# 1_BLE.net
KiCad netlist of a schematic drawn in Altium Designer
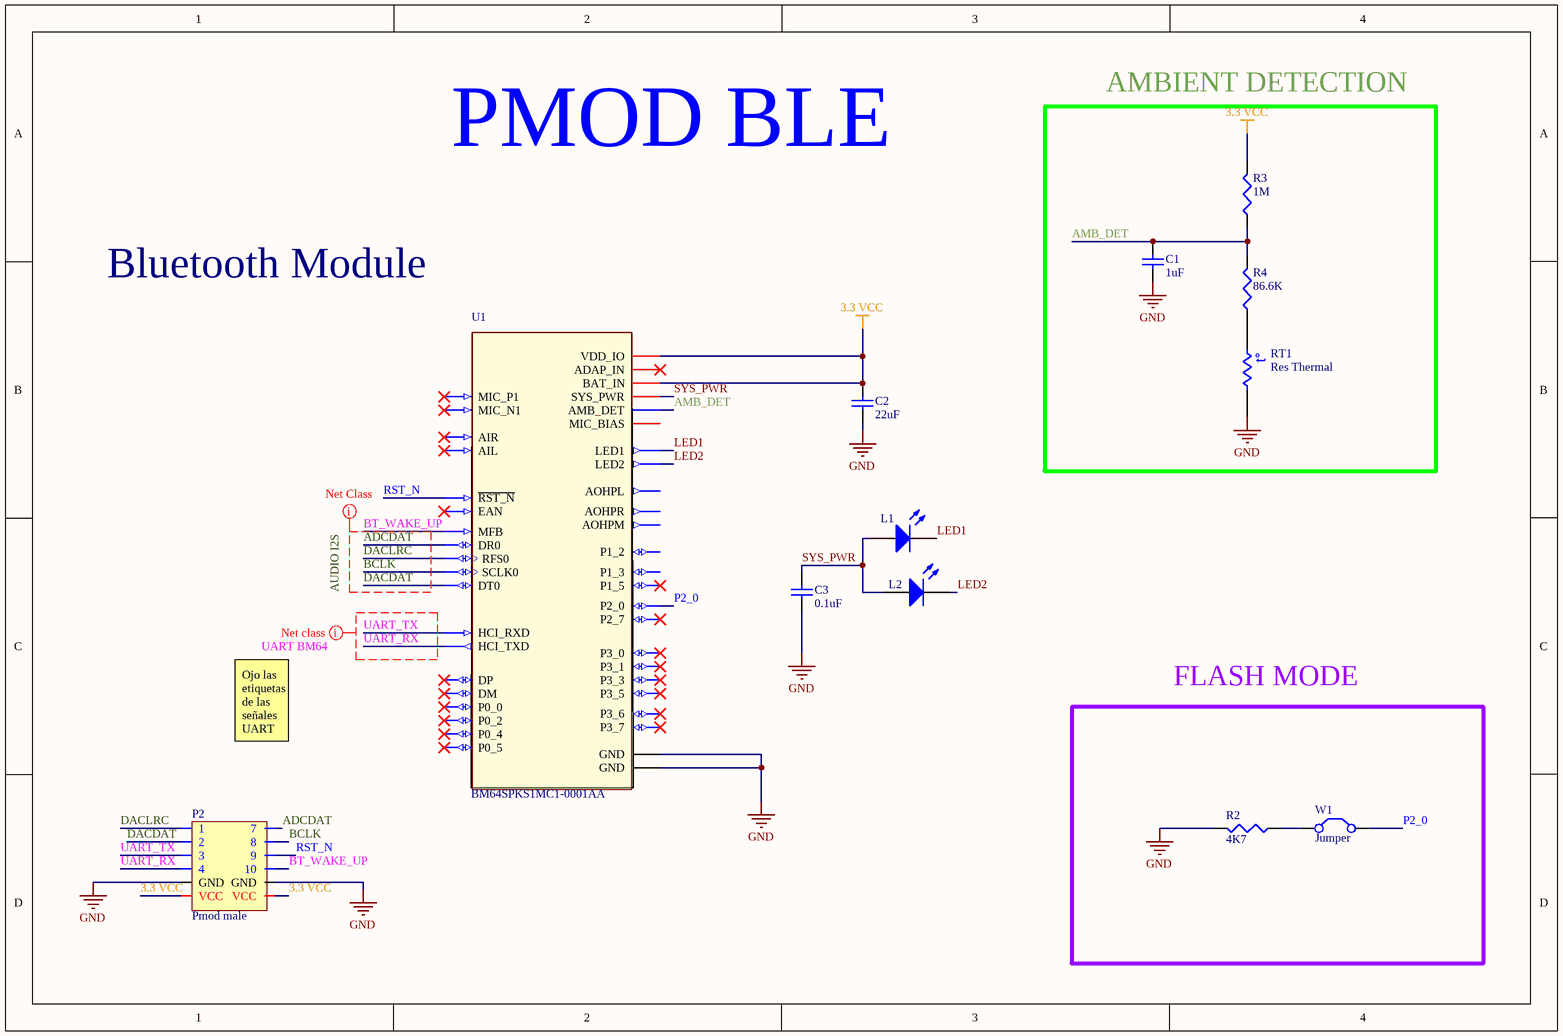
[diagram p0: 1_BLE.SchDoc]

(export (version "E")
  (design (tool "Eeschema 10.0.6"))
  (components
    (comp (ref "C1")
      (value "1uF")
      (footprint "Cap0805")
      (description "capacitor")
      (fields (field (name "ASID PART NUMBER") "C-AS"))
      (libsource (lib "navid2015") (part "Cap"))
    )
    (comp (ref "C2")
      (value "22uF")
      (footprint "C1210")
      (description "Capacitor (Semiconductor SIM Model)")
      (fields (field (name "Comment") "Cap Semi") (field (name "PUBLISHER") "Altium Limited"))
      (libsource (lib "Miscellaneous Devices") (part "Cap Semi"))
    )
    (comp (ref "C3")
      (value "0.1uF")
      (footprint "Cap0805")
      (description "capacitor")
      (fields (field (name "ASID PART NUMBER") "C-AS"))
      (libsource (lib "navid2015") (part "Cap"))
    )
    (comp (ref "L1")
      (value "LED1")
      (footprint "Diode1206")
      (description "Typical RED GaAs LED")
      (fields (field (name "PUBLISHER") "Altium Limited"))
      (libsource (lib "Miscellaneous Devices") (part "LED1"))
    )
    (comp (ref "L2")
      (value "LED1")
      (footprint "Diode1206")
      (description "Typical RED GaAs LED")
      (fields (field (name "PUBLISHER") "Altium Limited"))
      (libsource (lib "Miscellaneous Devices") (part "LED1"))
    )
    (comp (ref "P2")
      (value "Pmod male")
      (footprint "901220766")
      (description "p mod male 6 position 2 rows")
      (libsource (lib "Schlib1") (part "Pmod male"))
    )
    (comp (ref "R2")
      (value "4K7")
      (footprint "Resistor 0805")
      (description "Resistor")
      (fields (field (name "Comment") "Res3") (field (name "PUBLISHER") "Altium Limited"))
      (libsource (lib "Miscellaneous Devices") (part "Res3"))
    )
    (comp (ref "R3")
      (value "1M")
      (footprint "Resistor 0805")
      (description "Resistor")
      (fields (field (name "Comment") "Res3") (field (name "PUBLISHER") "Altium Limited"))
      (libsource (lib "Miscellaneous Devices") (part "Res3"))
    )
    (comp (ref "R4")
      (value "86.6K")
      (footprint "Resistor 0805")
      (description "Resistor")
      (fields (field (name "Comment") "Res3") (field (name "PUBLISHER") "Altium Limited"))
      (libsource (lib "Miscellaneous Devices") (part "Res3"))
    )
    (comp (ref "RT1")
      (value "Res Thermal")
      (footprint "6-0805_N")
      (description "Thermistor")
      (fields (field (name "PUBLISHER") "Altium Limited"))
      (libsource (lib "Miscellaneous Devices") (part "Res Thermal"))
    )
    (comp (ref "U1")
      (value "BM64SPKS1MC1-0001AA")
      (footprint "*MODULE_BM64SPKS1MC1-0001AA")
      (description "Bluetooth Bluetooth v5.0 Transceiver Module 2.4GHz Integrated, Trace Surface Mount")
      (fields (field (name "MF") "Microchip"))
      (libsource (lib "Schlib1") (part "BM64SPKS1MC1-0001AA"))
    )
    (comp (ref "W1")
      (value "Jumper")
      (footprint "Shunt jumper")
      (description "Jumper Wire")
      (fields (field (name "PUBLISHER") "Altium Limited"))
      (libsource (lib "Miscellaneous Devices") (part "Jumper"))
    )
  )
  (nets
    (net (code "1") (name "/ADCDAT") (class "Default")
      (node (ref "P2") (pin "7") (pinfunction "7_7") (pintype "passive"))
      (node (ref "U1") (pin "1") (pinfunction "DR0_1") (pintype "bidirectional"))
    )
    (net (code "2") (name "/AMB_DET") (class "Default")
      (node (ref "C1") (pin "2") (pinfunction "2_2") (pintype "passive"))
      (node (ref "R3") (pin "1") (pinfunction "1_1") (pintype "passive"))
      (node (ref "R4") (pin "2") (pinfunction "2_2") (pintype "passive"))
      (node (ref "U1") (pin "25") (pinfunction "AMB_DET_25") (pintype "power_in"))
    )
    (net (code "3") (name "/BCLK") (class "Default")
      (node (ref "P2") (pin "8") (pinfunction "8_8") (pintype "passive"))
      (node (ref "U1") (pin "3") (pinfunction "SCLK0_3") (pintype "bidirectional"))
    )
    (net (code "4") (name "/BT_WAKE_UP") (class "Default")
      (node (ref "P2") (pin "10") (pinfunction "10_10") (pintype "passive"))
      (node (ref "U1") (pin "26") (pinfunction "MFB_26") (pintype "input"))
    )
    (net (code "5") (name "/DACDAT") (class "Default")
      (node (ref "P2") (pin "2") (pinfunction "2_2") (pintype "passive"))
      (node (ref "U1") (pin "4") (pinfunction "DT0_4") (pintype "bidirectional"))
    )
    (net (code "6") (name "/DACLRC") (class "Default")
      (node (ref "P2") (pin "1") (pinfunction "1_1") (pintype "passive"))
      (node (ref "U1") (pin "2") (pinfunction "RFS0_2") (pintype "bidirectional"))
    )
    (net (code "7") (name "/LED1") (class "Default")
      (node (ref "L1") (pin "2") (pinfunction "K_2") (pintype "passive"))
      (node (ref "U1") (pin "28") (pinfunction "LED1_28") (pintype "output"))
    )
    (net (code "8") (name "/LED2") (class "Default")
      (node (ref "L2") (pin "2") (pinfunction "K_2") (pintype "passive"))
      (node (ref "U1") (pin "27") (pinfunction "LED2_27") (pintype "output"))
    )
    (net (code "9") (name "/P2_0") (class "Default")
      (node (ref "U1") (pin "41") (pinfunction "P2_0_41") (pintype "bidirectional"))
      (node (ref "W1") (pin "2") (pinfunction "C2_2") (pintype "passive"))
    )
    (net (code "10") (name "/RST_N") (class "Default")
      (node (ref "P2") (pin "9") (pinfunction "9_9") (pintype "passive"))
      (node (ref "U1") (pin "13") (pinfunction "~{RST_N}_13") (pintype "input"))
    )
    (net (code "11") (name "/SYS_PWR") (class "Default")
      (node (ref "C3") (pin "1") (pinfunction "1_1") (pintype "passive"))
      (node (ref "L1") (pin "1") (pinfunction "A_1") (pintype "passive"))
      (node (ref "L2") (pin "1") (pinfunction "A_1") (pintype "passive"))
      (node (ref "U1") (pin "24") (pinfunction "SYS_PWR_24") (pintype "power_in"))
    )
    (net (code "12") (name "/UART_RX") (class "Default")
      (node (ref "P2") (pin "4") (pinfunction "4_4") (pintype "passive"))
      (node (ref "U1") (pin "20") (pinfunction "HCI_TXD_20") (pintype "output"))
    )
    (net (code "13") (name "/UART_TX") (class "Default")
      (node (ref "P2") (pin "3") (pinfunction "3_3") (pintype "passive"))
      (node (ref "U1") (pin "19") (pinfunction "HCI_RXD_19") (pintype "input"))
    )
    (net (code "14") (name "3.3 VCC") (class "Default")
      (node (ref "C2") (pin "2") (pinfunction "2_2") (pintype "passive"))
      (node (ref "P2") (pin "12") (pinfunction "VCC_12") (pintype "passive"))
      (node (ref "P2") (pin "6") (pinfunction "VCC_6") (pintype "passive"))
      (node (ref "R3") (pin "2") (pinfunction "2_2") (pintype "passive"))
      (node (ref "U1") (pin "21") (pinfunction "VDD_IO_21") (pintype "power_in"))
      (node (ref "U1") (pin "22") (pinfunction "BAT_IN_22") (pintype "power_in"))
    )
    (net (code "15") (name "GND") (class "Default")
      (node (ref "C1") (pin "1") (pinfunction "1_1") (pintype "passive"))
      (node (ref "C2") (pin "1") (pinfunction "1_1") (pintype "passive"))
      (node (ref "C3") (pin "2") (pinfunction "2_2") (pintype "passive"))
      (node (ref "P2") (pin "11") (pinfunction "GND_11") (pintype "passive"))
      (node (ref "P2") (pin "5") (pinfunction "GND_5") (pintype "passive"))
      (node (ref "R2") (pin "2") (pinfunction "2_2") (pintype "passive"))
      (node (ref "RT1") (pin "2") (pinfunction "2_2") (pintype "passive"))
      (node (ref "U1") (pin "14") (pinfunction "GND_14") (pintype "power_in"))
      (node (ref "U1") (pin "43") (pinfunction "GND_43") (pintype "power_in"))
    )
    (net (code "16") (name "Net-(R4-Pad1)") (class "Default")
      (node (ref "R4") (pin "1") (pinfunction "1_1") (pintype "passive"))
      (node (ref "RT1") (pin "1") (pinfunction "1_1") (pintype "passive"))
    )
    (net (code "17") (name "Net-(W1-C1)") (class "Default")
      (node (ref "R2") (pin "1") (pinfunction "1_1") (pintype "passive"))
      (node (ref "W1") (pin "1") (pinfunction "C1_1") (pintype "passive"))
    )
    (net (code "18") (name "unconnected-(U1-ADAP_IN-Pad23)") (class "Default")
      (node (ref "U1") (pin "23") (pinfunction "ADAP_IN_23") (pintype "power_in+no_connect"))
    )
    (net (code "19") (name "unconnected-(U1-AIL-Pad12)") (class "Default")
      (node (ref "U1") (pin "12") (pinfunction "AIL_12") (pintype "input+no_connect"))
    )
    (net (code "20") (name "unconnected-(U1-AIR-Pad11)") (class "Default")
      (node (ref "U1") (pin "11") (pinfunction "AIR_11") (pintype "input+no_connect"))
    )
    (net (code "21") (name "unconnected-(U1-AOHPL-Pad7)") (class "Default")
      (node (ref "U1") (pin "7") (pinfunction "AOHPL_7") (pintype "output"))
    )
    (net (code "22") (name "unconnected-(U1-AOHPM-Pad6)") (class "Default")
      (node (ref "U1") (pin "6") (pinfunction "AOHPM_6") (pintype "output"))
    )
    (net (code "23") (name "unconnected-(U1-AOHPR-Pad5)") (class "Default")
      (node (ref "U1") (pin "5") (pinfunction "AOHPR_5") (pintype "output"))
    )
    (net (code "24") (name "unconnected-(U1-DM-Pad33)") (class "Default")
      (node (ref "U1") (pin "33") (pinfunction "DM_33") (pintype "bidirectional+no_connect"))
    )
    (net (code "25") (name "unconnected-(U1-DP-Pad34)") (class "Default")
      (node (ref "U1") (pin "34") (pinfunction "DP_34") (pintype "bidirectional+no_connect"))
    )
    (net (code "26") (name "unconnected-(U1-EAN-Pad32)") (class "Default")
      (node (ref "U1") (pin "32") (pinfunction "EAN_32") (pintype "input+no_connect"))
    )
    (net (code "27") (name "unconnected-(U1-MIC_BIAS-Pad10)") (class "Default")
      (node (ref "U1") (pin "10") (pinfunction "MIC_BIAS_10") (pintype "power_in"))
    )
    (net (code "28") (name "unconnected-(U1-MIC_N1-Pad8)") (class "Default")
      (node (ref "U1") (pin "8") (pinfunction "MIC_N1_8") (pintype "input+no_connect"))
    )
    (net (code "29") (name "unconnected-(U1-MIC_P1-Pad9)") (class "Default")
      (node (ref "U1") (pin "9") (pinfunction "MIC_P1_9") (pintype "input+no_connect"))
    )
    (net (code "30") (name "unconnected-(U1-P0_0-Pad31)") (class "Default")
      (node (ref "U1") (pin "31") (pinfunction "P0_0_31") (pintype "bidirectional+no_connect"))
    )
    (net (code "31") (name "unconnected-(U1-P0_2-Pad40)") (class "Default")
      (node (ref "U1") (pin "40") (pinfunction "P0_2_40") (pintype "bidirectional+no_connect"))
    )
    (net (code "32") (name "unconnected-(U1-P0_4-Pad17)") (class "Default")
      (node (ref "U1") (pin "17") (pinfunction "P0_4_17") (pintype "bidirectional+no_connect"))
    )
    (net (code "33") (name "unconnected-(U1-P0_5-Pad35)") (class "Default")
      (node (ref "U1") (pin "35") (pinfunction "P0_5_35") (pintype "bidirectional+no_connect"))
    )
    (net (code "34") (name "unconnected-(U1-P1_2-Pad15)") (class "Default")
      (node (ref "U1") (pin "15") (pinfunction "P1_2_15") (pintype "bidirectional"))
    )
    (net (code "35") (name "unconnected-(U1-P1_3-Pad16)") (class "Default")
      (node (ref "U1") (pin "16") (pinfunction "P1_3_16") (pintype "bidirectional"))
    )
    (net (code "36") (name "unconnected-(U1-P1_5-Pad18)") (class "Default")
      (node (ref "U1") (pin "18") (pinfunction "P1_5_18") (pintype "bidirectional+no_connect"))
    )
    (net (code "37") (name "unconnected-(U1-P2_7-Pad42)") (class "Default")
      (node (ref "U1") (pin "42") (pinfunction "P2_7_42") (pintype "bidirectional+no_connect"))
    )
    (net (code "38") (name "unconnected-(U1-P3_0-Pad36)") (class "Default")
      (node (ref "U1") (pin "36") (pinfunction "P3_0_36") (pintype "bidirectional+no_connect"))
    )
    (net (code "39") (name "unconnected-(U1-P3_1-Pad37)") (class "Default")
      (node (ref "U1") (pin "37") (pinfunction "P3_1_37") (pintype "bidirectional+no_connect"))
    )
    (net (code "40") (name "unconnected-(U1-P3_3-Pad38)") (class "Default")
      (node (ref "U1") (pin "38") (pinfunction "P3_3_38") (pintype "bidirectional+no_connect"))
    )
    (net (code "41") (name "unconnected-(U1-P3_5-Pad30)") (class "Default")
      (node (ref "U1") (pin "30") (pinfunction "P3_5_30") (pintype "bidirectional+no_connect"))
    )
    (net (code "42") (name "unconnected-(U1-P3_6-Pad39)") (class "Default")
      (node (ref "U1") (pin "39") (pinfunction "P3_6_39") (pintype "bidirectional+no_connect"))
    )
    (net (code "43") (name "unconnected-(U1-P3_7-Pad29)") (class "Default")
      (node (ref "U1") (pin "29") (pinfunction "P3_7_29") (pintype "bidirectional+no_connect"))
    )
  )
)
